# 3V-Switcher-50mA.net
KiCad netlist of a schematic drawn in Altium Designer
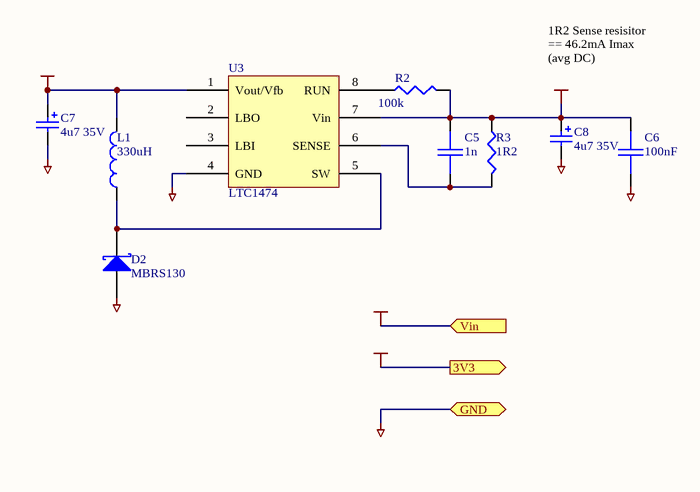
[diagram p0: 3V-Switcher-50mA.SCHDOC]

(export (version "E")
  (design (tool "Eeschema 10.0.6"))
  (components
    (comp (ref "C5")
      (value "1n")
      (footprint "0603")
      (description "Capacitor")
      (libsource (lib "Miscellaneous Devices") (part "CAP"))
    )
    (comp (ref "C6")
      (value "100nF")
      (footprint "0603")
      (description "Capacitor")
      (libsource (lib "Miscellaneous Devices") (part "CAP"))
    )
    (comp (ref "C7")
      (value "4u7 35V")
      (footprint "MCCT-CASEC")
      (description "Polarized Capacitor (Surface Mount)")
      (libsource (lib "Miscellaneous Devices") (part "Cap Pol3"))
    )
    (comp (ref "C8")
      (value "4u7 35V")
      (footprint "MCCT-CASEC")
      (description "Polarized Capacitor (Surface Mount)")
      (libsource (lib "Miscellaneous Devices") (part "Cap Pol3"))
    )
    (comp (ref "D2")
      (value "MBRS130")
      (footprint "SMB")
      (description "Schottky Diode")
      (libsource (lib "RCLDQ") (part "D SCHOTTKY"))
    )
    (comp (ref "L1")
      (value "330uH")
      (footprint "1812")
      (description "Inductor")
      (libsource (lib "Miscellaneous Devices") (part "Inductor"))
    )
    (comp (ref "R2")
      (value "100k")
      (footprint "0603")
      (description "Resistor")
      (libsource (lib "RCLDQ") (part "RES1"))
    )
    (comp (ref "R3")
      (value "1R2")
      (footprint "0603")
      (description "Resistor")
      (libsource (lib "Miscellaneous Devices") (part "RES1"))
    )
    (comp (ref "U3")
      (value "LTC1474")
      (footprint "TSOP8")
      (description "Step-down converter")
      (libsource (lib "MiscellaneousIC") (part "LTC1474"))
    )
  )
  (nets
    (net (code "1") (name "3V3") (class "Default")
      (node (ref "C7") (pin "1") (pinfunction "1_1") (pintype "passive"))
      (node (ref "L1") (pin "2") (pinfunction "2_2") (pintype "passive"))
      (node (ref "U3") (pin "1") (pinfunction "Vout/Vfb_1") (pintype "passive"))
    )
    (net (code "2") (name "GND") (class "Default")
      (node (ref "C6") (pin "2") (pinfunction "2_2") (pintype "passive"))
      (node (ref "C7") (pin "2") (pinfunction "2_2") (pintype "passive"))
      (node (ref "C8") (pin "2") (pinfunction "2_2") (pintype "passive"))
      (node (ref "D2") (pin "A") (pinfunction "A_A") (pintype "passive"))
      (node (ref "U3") (pin "4") (pinfunction "GND_4") (pintype "passive"))
    )
    (net (code "3") (name "Net-(U3-RUN)") (class "Default")
      (node (ref "R2") (pin "1") (pinfunction "1_1") (pintype "passive"))
      (node (ref "U3") (pin "8") (pinfunction "RUN_8") (pintype "passive"))
    )
    (net (code "4") (name "Net-(U3-SENSE)") (class "Default")
      (node (ref "C5") (pin "2") (pinfunction "2_2") (pintype "passive"))
      (node (ref "R3") (pin "2") (pinfunction "2_2") (pintype "passive"))
      (node (ref "U3") (pin "6") (pinfunction "SENSE_6") (pintype "passive"))
    )
    (net (code "5") (name "Net-(U3-SW)") (class "Default")
      (node (ref "D2") (pin "K") (pinfunction "K_K") (pintype "passive"))
      (node (ref "L1") (pin "1") (pinfunction "1_1") (pintype "passive"))
      (node (ref "U3") (pin "5") (pinfunction "SW_5") (pintype "passive"))
    )
    (net (code "6") (name "Vin") (class "Default")
      (node (ref "C5") (pin "1") (pinfunction "1_1") (pintype "passive"))
      (node (ref "C6") (pin "1") (pinfunction "1_1") (pintype "passive"))
      (node (ref "C8") (pin "1") (pinfunction "1_1") (pintype "passive"))
      (node (ref "R2") (pin "2") (pinfunction "2_2") (pintype "passive"))
      (node (ref "R3") (pin "1") (pinfunction "1_1") (pintype "passive"))
      (node (ref "U3") (pin "7") (pinfunction "Vin_7") (pintype "passive"))
    )
    (net (code "7") (name "unconnected-(U3-LBI-Pad3)") (class "Default")
      (node (ref "U3") (pin "3") (pinfunction "LBI_3") (pintype "passive"))
    )
    (net (code "8") (name "unconnected-(U3-LBO-Pad2)") (class "Default")
      (node (ref "U3") (pin "2") (pinfunction "LBO_2") (pintype "passive"))
    )
  )
)
